# Audio.net
KiCad netlist of a schematic drawn in Altium Designer
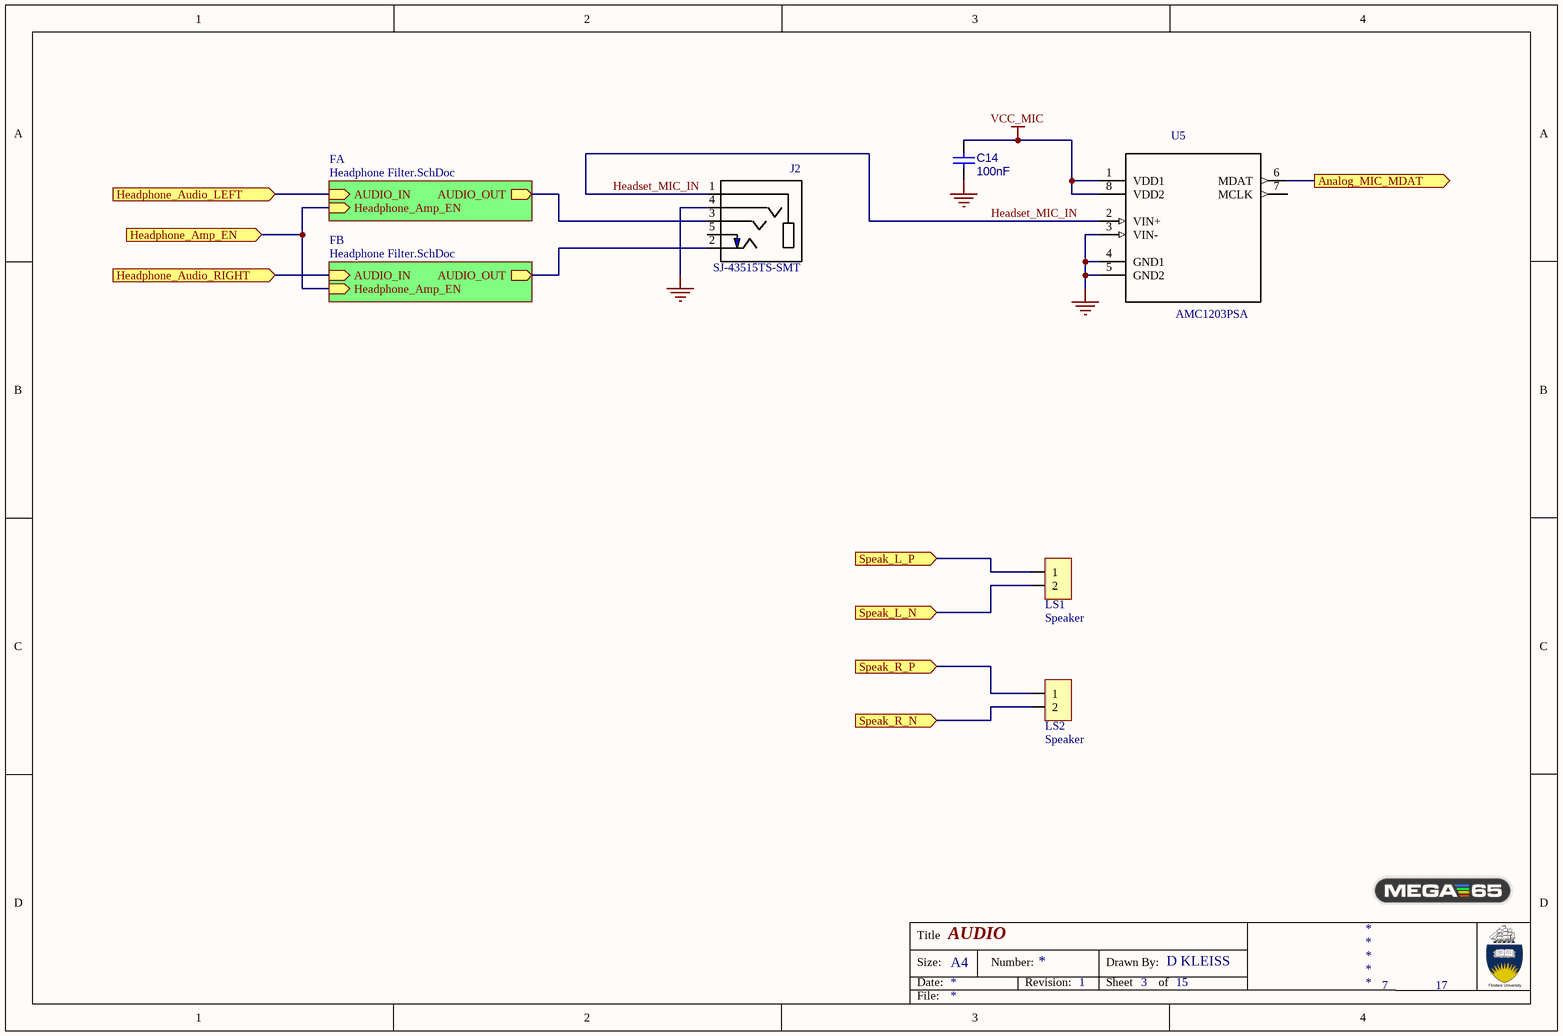
[diagram p0: Audio.SchDoc]

(export (version "E")
  (design (tool "Eeschema 10.0.6"))
  (components
    (comp (ref "C14")
      (value "100nF")
      (footprint "0603_CAP UF HD")
      (description "Capacitor")
      (libsource (lib "Workshop Library 2010_06_24") (part "Cap"))
    )
    (comp (ref "J2")
      (value "SJ-43515TS-SMT")
      (footprint "SOCKET 3.5 TRRS CUI_SJ-43515TS-SMT")
      (description "SJ Series 3.5 mm 16 V 4 Conductor SMT Mid Mount Stereo Audio Jack")
      (fields (field (name "MANUFACTURER") "CUI"))
      (libsource (lib "SJ-43515TS-SMT") (part "SJ-43515TS-SMT"))
    )
    (comp (ref "LS1")
      (value "Speaker")
      (footprint "HDR1X2")
      (libsource (lib "Workshop Library 2010_06_24") (part "CON2"))
    )
    (comp (ref "LS2")
      (value "Speaker")
      (footprint "HDR1X2")
      (libsource (lib "Workshop Library 2010_06_24") (part "CON2"))
    )
    (comp (ref "U5")
      (value "AMC1203PSA")
      (footprint "AMC1203")
      (description "Single Channel Single ADC Delta-Sigma 40ksps 16-bit Serial 8-Pin SOP Tube")
      (fields (field (name "MANUFACTURER") "Texas Instruments"))
      (libsource (lib "AMC1203PSA") (part "AMC1203PSA"))
    )
  )
  (nets
    (net (code "1") (name "/AUDIO_OUT") (class "Default")
      (node (ref "J2") (pin "2") (pinfunction "TIP_2") (pintype "passive"))
    )
    (net (code "2") (name "/AUDIO_OUT_1") (class "Default")
      (node (ref "J2") (pin "3") (pinfunction "RING1_3") (pintype "passive"))
    )
    (net (code "3") (name "/Analog_MIC_MDAT") (class "Default")
      (node (ref "U5") (pin "6") (pinfunction "MDAT_6") (pintype "output"))
    )
    (net (code "7") (name "/Headset_MIC_IN") (class "Default")
      (node (ref "J2") (pin "1") (pinfunction "SLEEVE_1") (pintype "passive"))
      (node (ref "U5") (pin "2") (pinfunction "VIN+_2") (pintype "input"))
    )
    (net (code "8") (name "/Speak_L_N") (class "Default")
      (node (ref "LS1") (pin "2") (pinfunction "2_2") (pintype "passive"))
    )
    (net (code "9") (name "/Speak_L_P") (class "Default")
      (node (ref "LS1") (pin "1") (pinfunction "1_1") (pintype "passive"))
    )
    (net (code "10") (name "/Speak_R_N") (class "Default")
      (node (ref "LS2") (pin "2") (pinfunction "2_2") (pintype "passive"))
    )
    (net (code "11") (name "/Speak_R_P") (class "Default")
      (node (ref "LS2") (pin "1") (pinfunction "1_1") (pintype "passive"))
    )
    (net (code "12") (name "GND") (class "Default")
      (node (ref "C14") (pin "2") (pinfunction "2_2") (pintype "passive"))
      (node (ref "J2") (pin "4") (pinfunction "RING2_4") (pintype "passive"))
      (node (ref "U5") (pin "3") (pinfunction "VIN-_3") (pintype "input"))
      (node (ref "U5") (pin "4") (pinfunction "GND1_4") (pintype "passive"))
      (node (ref "U5") (pin "5") (pinfunction "GND2_5") (pintype "passive"))
    )
    (net (code "13") (name "VCC_MIC") (class "Default")
      (node (ref "C14") (pin "1") (pinfunction "1_1") (pintype "passive"))
      (node (ref "U5") (pin "1") (pinfunction "VDD1_1") (pintype "power_in"))
      (node (ref "U5") (pin "8") (pinfunction "VDD2_8") (pintype "power_in"))
    )
    (net (code "14") (name "unconnected-(J2-TIP_SWITCH-Pad5)") (class "Default")
      (node (ref "J2") (pin "5") (pinfunction "TIP_SWITCH_5") (pintype "passive"))
    )
    (net (code "15") (name "unconnected-(U5-MCLK-Pad7)") (class "Default")
      (node (ref "U5") (pin "7") (pinfunction "MCLK_7") (pintype "output"))
    )
  )
)
